# tyl.net
KiCad netlist of a schematic drawn in EAGLE
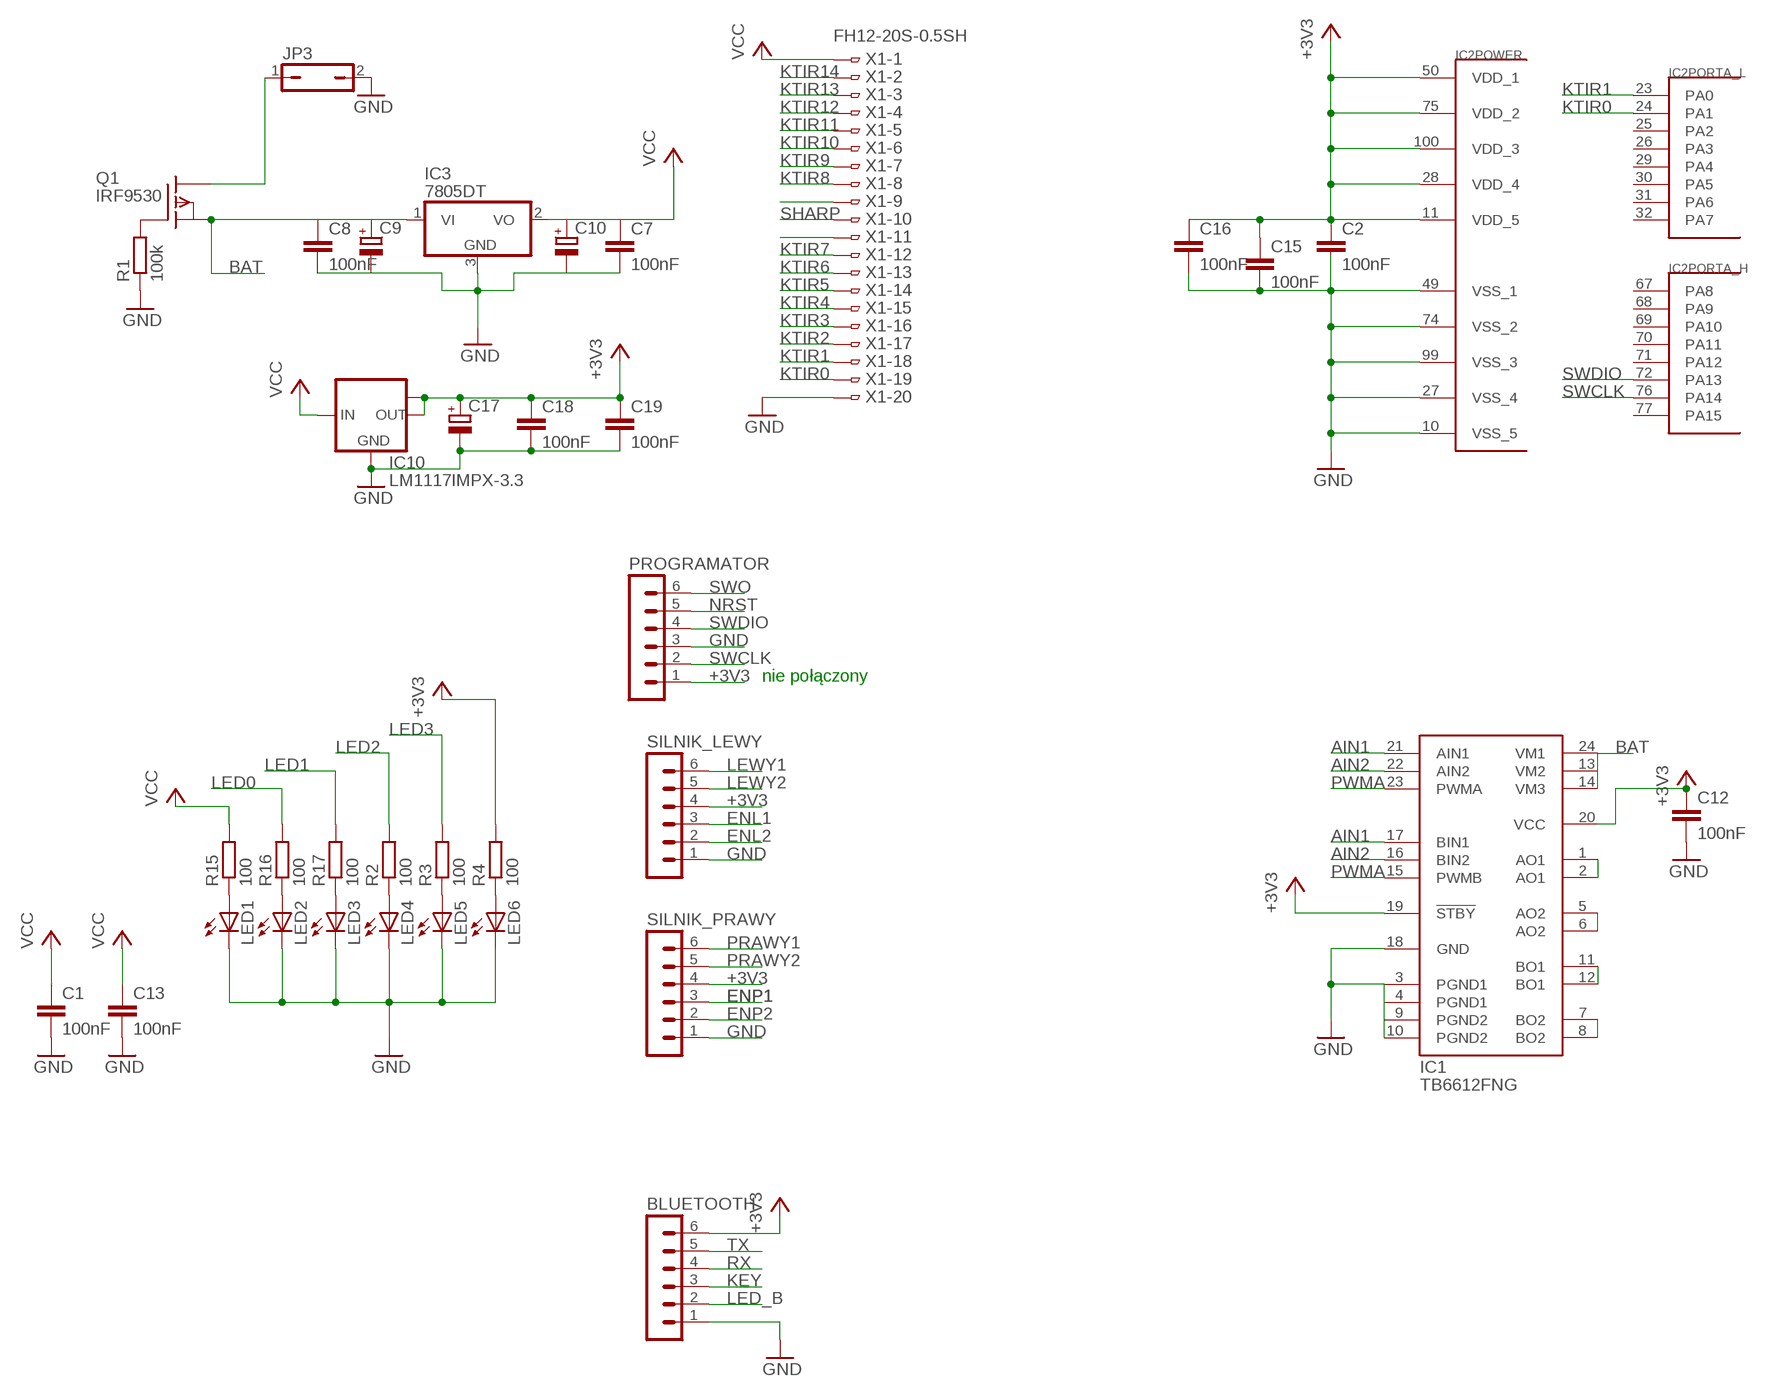
[diagram p0: schematic, sheet 1, part 1 of 2]
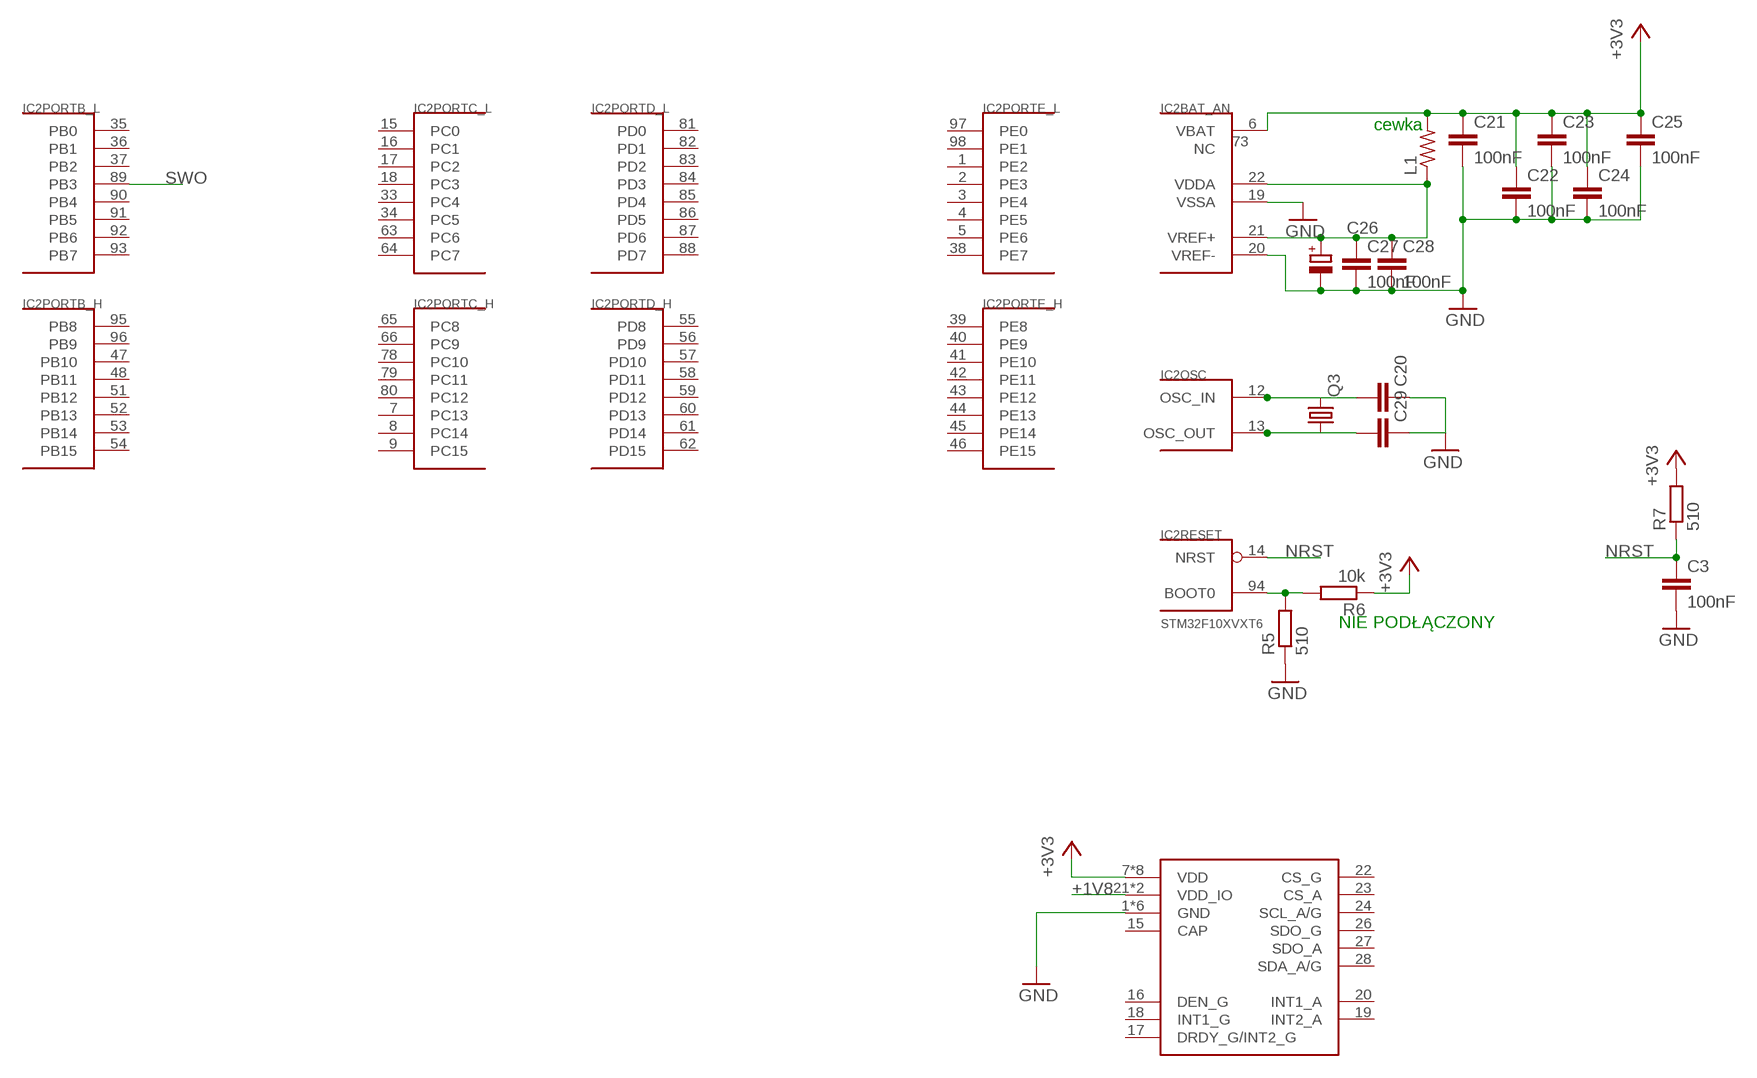
[diagram p1: schematic, sheet 1, part 2 of 2]

(export (version "E")
  (design (tool "Eeschema 10.0.6"))
  (components
    (comp (ref "BLUETOOTH")
      (value "MA06-1")
      (footprint "eagle-import:MA06-1")
      (libsource (lib "eagle-import") (part "MA06-1"))
    )
    (comp (ref "C1")
      (value "100nF")
      (footprint "eagle-import:C0603")
      (libsource (lib "eagle-import") (part "C-EUC0603"))
    )
    (comp (ref "C2")
      (value "100nF")
      (footprint "eagle-import:C0603")
      (libsource (lib "eagle-import") (part "C-EUC0603"))
    )
    (comp (ref "C3")
      (value "100nF")
      (footprint "eagle-import:C0603")
      (libsource (lib "eagle-import") (part "C-EUC0603"))
    )
    (comp (ref "C7")
      (value "100nF")
      (footprint "eagle-import:C0603")
      (libsource (lib "eagle-import") (part "C-EUC0603"))
    )
    (comp (ref "C8")
      (value "100nF")
      (footprint "eagle-import:C0603")
      (libsource (lib "eagle-import") (part "C-EUC0603"))
    )
    (comp (ref "C9")
      (value "CPOL-EUSMCA")
      (footprint "eagle-import:SMC_A")
      (libsource (lib "eagle-import") (part "CPOL-EUSMCA"))
    )
    (comp (ref "C10")
      (value "CPOL-EUSMCA")
      (footprint "eagle-import:SMC_A")
      (libsource (lib "eagle-import") (part "CPOL-EUSMCA"))
    )
    (comp (ref "C12")
      (value "100nF")
      (footprint "eagle-import:C0603")
      (libsource (lib "eagle-import") (part "C-EUC0603"))
    )
    (comp (ref "C13")
      (value "100nF")
      (footprint "eagle-import:C0603")
      (libsource (lib "eagle-import") (part "C-EUC0603"))
    )
    (comp (ref "C15")
      (value "100nF")
      (footprint "eagle-import:C0603")
      (libsource (lib "eagle-import") (part "C-EUC0603"))
    )
    (comp (ref "C16")
      (value "100nF")
      (footprint "eagle-import:C0603")
      (libsource (lib "eagle-import") (part "C-EUC0603"))
    )
    (comp (ref "C17")
      (value "CPOL-EUSMCA")
      (footprint "eagle-import:SMC_A")
      (libsource (lib "eagle-import") (part "CPOL-EUSMCA"))
    )
    (comp (ref "C18")
      (value "100nF")
      (footprint "eagle-import:C0603")
      (libsource (lib "eagle-import") (part "C-EUC0603"))
    )
    (comp (ref "C19")
      (value "100nF")
      (footprint "eagle-import:C0603")
      (libsource (lib "eagle-import") (part "C-EUC0603"))
    )
    (comp (ref "C20")
      (value "C-EUC0603")
      (footprint "eagle-import:C0603")
      (libsource (lib "eagle-import") (part "C-EUC0603"))
    )
    (comp (ref "C21")
      (value "100nF")
      (footprint "eagle-import:C0603")
      (libsource (lib "eagle-import") (part "C-EUC0603"))
    )
    (comp (ref "C22")
      (value "100nF")
      (footprint "eagle-import:C0603")
      (libsource (lib "eagle-import") (part "C-EUC0603"))
    )
    (comp (ref "C23")
      (value "100nF")
      (footprint "eagle-import:C0603")
      (libsource (lib "eagle-import") (part "C-EUC0603"))
    )
    (comp (ref "C24")
      (value "100nF")
      (footprint "eagle-import:C0603")
      (libsource (lib "eagle-import") (part "C-EUC0603"))
    )
    (comp (ref "C25")
      (value "100nF")
      (footprint "eagle-import:C0603")
      (libsource (lib "eagle-import") (part "C-EUC0603"))
    )
    (comp (ref "C26")
      (value "CPOL-EUSMCA")
      (footprint "eagle-import:SMC_A")
      (libsource (lib "eagle-import") (part "CPOL-EUSMCA"))
    )
    (comp (ref "C27")
      (value "100nF")
      (footprint "eagle-import:C0603")
      (libsource (lib "eagle-import") (part "C-EUC0603"))
    )
    (comp (ref "C28")
      (value "100nF")
      (footprint "eagle-import:C0603")
      (libsource (lib "eagle-import") (part "C-EUC0603"))
    )
    (comp (ref "C29")
      (value "C-EUC0603")
      (footprint "eagle-import:C0603")
      (libsource (lib "eagle-import") (part "C-EUC0603"))
    )
    (comp (ref "IC1")
      (value "TB6612FNG")
      (footprint "eagle-import:SSOP24")
      (libsource (lib "eagle-import") (part "TB6612FNG"))
    )
    (comp (ref "IC2")
      (value "STM32F10XVXT6")
      (footprint "eagle-import:TQFP100")
      (libsource (lib "eagle-import") (part "STM32F10XVXT6"))
    )
    (comp (ref "IC3")
      (value "7805DT")
      (footprint "eagle-import:TO252")
      (libsource (lib "eagle-import") (part "78DT05"))
    )
    (comp (ref "IC10")
      (value "LM1117IMPX-3.3")
      (footprint "eagle-import:SOT223")
      (libsource (lib "eagle-import") (part "LM1117IMPX-3.3"))
    )
    (comp (ref "JP3")
      (value "JP1Q")
      (footprint "eagle-import:JP1")
      (libsource (lib "eagle-import") (part "JP1Q"))
    )
    (comp (ref "L1")
      (value "R-US_R0805")
      (footprint "eagle-import:R0805")
      (libsource (lib "eagle-import") (part "R-US_R0805"))
    )
    (comp (ref "LED1")
      (value "LEDSML0805")
      (footprint "eagle-import:SML0805")
      (libsource (lib "eagle-import") (part "LEDSML0805"))
    )
    (comp (ref "LED2")
      (value "LEDSML0805")
      (footprint "eagle-import:SML0805")
      (libsource (lib "eagle-import") (part "LEDSML0805"))
    )
    (comp (ref "LED3")
      (value "LEDSML0805")
      (footprint "eagle-import:SML0805")
      (libsource (lib "eagle-import") (part "LEDSML0805"))
    )
    (comp (ref "LED4")
      (value "LEDSML0805")
      (footprint "eagle-import:SML0805")
      (libsource (lib "eagle-import") (part "LEDSML0805"))
    )
    (comp (ref "LED5")
      (value "LEDSML0805")
      (footprint "eagle-import:SML0805")
      (libsource (lib "eagle-import") (part "LEDSML0805"))
    )
    (comp (ref "LED6")
      (value "LEDSML0805")
      (footprint "eagle-import:SML0805")
      (libsource (lib "eagle-import") (part "LEDSML0805"))
    )
    (comp (ref "PROGRAMATOR")
      (value "MA06-1")
      (footprint "eagle-import:MA06-1")
      (libsource (lib "eagle-import") (part "MA06-1"))
    )
    (comp (ref "Q1")
      (value "IRF9530")
      (footprint "eagle-import:TO220")
      (libsource (lib "eagle-import") (part "IRF9530"))
    )
    (comp (ref "Q3")
      (value "CRYSTALSM49")
      (footprint "eagle-import:SM49")
      (libsource (lib "eagle-import") (part "CRYSTALSM49"))
    )
    (comp (ref "R1")
      (value "100k")
      (footprint "eagle-import:R0805")
      (libsource (lib "eagle-import") (part "R-EU_R0805"))
    )
    (comp (ref "R2")
      (value "100")
      (footprint "eagle-import:R0805")
      (libsource (lib "eagle-import") (part "R-EU_R0805"))
    )
    (comp (ref "R3")
      (value "100")
      (footprint "eagle-import:R0805")
      (libsource (lib "eagle-import") (part "R-EU_R0805"))
    )
    (comp (ref "R4")
      (value "100")
      (footprint "eagle-import:R0805")
      (libsource (lib "eagle-import") (part "R-EU_R0805"))
    )
    (comp (ref "R5")
      (value "510")
      (footprint "eagle-import:R0805")
      (libsource (lib "eagle-import") (part "R-EU_R0805"))
    )
    (comp (ref "R6")
      (value "10k")
      (footprint "eagle-import:R0805")
      (libsource (lib "eagle-import") (part "R-EU_R0805"))
    )
    (comp (ref "R7")
      (value "510")
      (footprint "eagle-import:R0805")
      (libsource (lib "eagle-import") (part "R-EU_R0805"))
    )
    (comp (ref "R15")
      (value "100")
      (footprint "eagle-import:R0805")
      (libsource (lib "eagle-import") (part "R-EU_R0805"))
    )
    (comp (ref "R16")
      (value "100")
      (footprint "eagle-import:R0805")
      (libsource (lib "eagle-import") (part "R-EU_R0805"))
    )
    (comp (ref "R17")
      (value "100")
      (footprint "eagle-import:R0805")
      (libsource (lib "eagle-import") (part "R-EU_R0805"))
    )
    (comp (ref "SILNIK_LEWY")
      (value "MA06-1")
      (footprint "eagle-import:MA06-1")
      (libsource (lib "eagle-import") (part "MA06-1"))
    )
    (comp (ref "SILNIK_PRAWY")
      (value "MA06-1")
      (footprint "eagle-import:MA06-1")
      (libsource (lib "eagle-import") (part "MA06-1"))
    )
    (comp (ref "U$1")
      (value "LSM330DLC")
      (footprint "eagle-import:LGA-28L")
      (libsource (lib "eagle-import") (part "LSM330DLC"))
    )
    (comp (ref "X1")
      (value "FH12-20S-0.5SH")
      (footprint "eagle-import:FH12-20S-0.5SH")
      (fields (field (name "MPN") "FH12-20S-0.5SH(55)"))
      (libsource (lib "eagle-import") (part "FH12-20S-0.5SH"))
    )
  )
  (nets
    (net (code "1") (name "+3V3") (class "Default")
      (node (ref "BLUETOOTH") (pin "6") (pinfunction "6_6") (pintype "passive"))
      (node (ref "C12") (pin "1") (pinfunction "1_1") (pintype "passive"))
      (node (ref "C15") (pin "1") (pinfunction "1_1") (pintype "passive"))
      (node (ref "C16") (pin "1") (pinfunction "1_1") (pintype "passive"))
      (node (ref "C17") (pin "+") (pinfunction "+_+") (pintype "passive"))
      (node (ref "C18") (pin "1") (pinfunction "1_1") (pintype "passive"))
      (node (ref "C19") (pin "1") (pinfunction "1_1") (pintype "passive"))
      (node (ref "C2") (pin "1") (pinfunction "1_1") (pintype "passive"))
      (node (ref "C21") (pin "1") (pinfunction "1_1") (pintype "passive"))
      (node (ref "C22") (pin "1") (pinfunction "1_1") (pintype "passive"))
      (node (ref "C23") (pin "1") (pinfunction "1_1") (pintype "passive"))
      (node (ref "C24") (pin "1") (pinfunction "1_1") (pintype "passive"))
      (node (ref "C25") (pin "1") (pinfunction "1_1") (pintype "passive"))
      (node (ref "IC1") (pin "19") (pinfunction "~{STBY}_19") (pintype "bidirectional"))
      (node (ref "IC1") (pin "20") (pinfunction "VCC_20") (pintype "bidirectional"))
      (node (ref "IC10") (pin "2") (pinfunction "OUT_2") (pintype "passive"))
      (node (ref "IC10") (pin "TAB") (pinfunction "OUT1_TAB") (pintype "passive"))
      (node (ref "IC2") (pin "100") (pinfunction "VDD_3_100") (pintype "power_in"))
      (node (ref "IC2") (pin "11") (pinfunction "VDD_5_11") (pintype "power_in"))
      (node (ref "IC2") (pin "28") (pinfunction "VDD_4_28") (pintype "power_in"))
      (node (ref "IC2") (pin "50") (pinfunction "VDD_1_50") (pintype "power_in"))
      (node (ref "IC2") (pin "6") (pinfunction "VBAT_6") (pintype "power_in"))
      (node (ref "IC2") (pin "75") (pinfunction "VDD_2_75") (pintype "power_in"))
      (node (ref "L1") (pin "2") (pinfunction "2_2") (pintype "passive"))
      (node (ref "PROGRAMATOR") (pin "1") (pinfunction "1_1") (pintype "passive"))
      (node (ref "R4") (pin "2") (pinfunction "2_2") (pintype "passive"))
      (node (ref "R6") (pin "1") (pinfunction "1_1") (pintype "passive"))
      (node (ref "R7") (pin "2") (pinfunction "2_2") (pintype "passive"))
      (node (ref "SILNIK_LEWY") (pin "4") (pinfunction "4_4") (pintype "passive"))
      (node (ref "SILNIK_PRAWY") (pin "4") (pinfunction "4_4") (pintype "passive"))
      (node (ref "U$1") (pin "10") (pinfunction "VDD_10") (pintype "power_in"))
      (node (ref "U$1") (pin "11") (pinfunction "VDD_11") (pintype "power_in"))
      (node (ref "U$1") (pin "12") (pinfunction "VDD_12") (pintype "power_in"))
      (node (ref "U$1") (pin "13") (pinfunction "VDD_13") (pintype "power_in"))
      (node (ref "U$1") (pin "14") (pinfunction "VDD_14") (pintype "power_in"))
      (node (ref "U$1") (pin "7") (pinfunction "VDD_7") (pintype "power_in"))
      (node (ref "U$1") (pin "8") (pinfunction "VDD_8") (pintype "power_in"))
      (node (ref "U$1") (pin "9") (pinfunction "VDD_9") (pintype "power_in"))
    )
    (net (code "2") (name "/+1V8") (class "Default")
      (node (ref "U$1") (pin "21") (pinfunction "VDD_IO_21") (pintype "power_in"))
      (node (ref "U$1") (pin "25") (pinfunction "VDD_IO_25") (pintype "power_in"))
    )
    (net (code "3") (name "/AIN1") (class "Default")
      (node (ref "IC1") (pin "17") (pinfunction "BIN1_17") (pintype "bidirectional"))
      (node (ref "IC1") (pin "21") (pinfunction "AIN1_21") (pintype "bidirectional"))
    )
    (net (code "4") (name "/AIN2") (class "Default")
      (node (ref "IC1") (pin "16") (pinfunction "BIN2_16") (pintype "bidirectional"))
      (node (ref "IC1") (pin "22") (pinfunction "AIN2_22") (pintype "bidirectional"))
    )
    (net (code "5") (name "/BAT") (class "Default")
      (node (ref "C8") (pin "1") (pinfunction "1_1") (pintype "passive"))
      (node (ref "C9") (pin "+") (pinfunction "+_+") (pintype "passive"))
      (node (ref "IC1") (pin "13") (pinfunction "VM2_13") (pintype "bidirectional"))
      (node (ref "IC1") (pin "14") (pinfunction "VM3_14") (pintype "bidirectional"))
      (node (ref "IC1") (pin "24") (pinfunction "VM1_24") (pintype "bidirectional"))
      (node (ref "IC3") (pin "1") (pinfunction "VI_1") (pintype "input"))
      (node (ref "Q1") (pin "3") (pinfunction "S_3") (pintype "passive"))
    )
    (net (code "6") (name "/ENL1") (class "Default")
      (node (ref "SILNIK_LEWY") (pin "3") (pinfunction "3_3") (pintype "passive"))
    )
    (net (code "7") (name "/ENL2") (class "Default")
      (node (ref "SILNIK_LEWY") (pin "2") (pinfunction "2_2") (pintype "passive"))
    )
    (net (code "8") (name "/ENP1") (class "Default")
      (node (ref "SILNIK_PRAWY") (pin "3") (pinfunction "3_3") (pintype "passive"))
    )
    (net (code "9") (name "/ENP2") (class "Default")
      (node (ref "SILNIK_PRAWY") (pin "2") (pinfunction "2_2") (pintype "passive"))
    )
    (net (code "10") (name "/KEY") (class "Default")
      (node (ref "BLUETOOTH") (pin "3") (pinfunction "3_3") (pintype "passive"))
    )
    (net (code "11") (name "/KTIR0") (class "Default")
      (node (ref "IC2") (pin "24") (pinfunction "PA1_24") (pintype "bidirectional"))
      (node (ref "X1") (pin "19") (pinfunction "1_19") (pintype "passive"))
    )
    (net (code "12") (name "/KTIR1") (class "Default")
      (node (ref "IC2") (pin "23") (pinfunction "PA0_23") (pintype "bidirectional"))
      (node (ref "X1") (pin "18") (pinfunction "1_18") (pintype "passive"))
    )
    (net (code "13") (name "/KTIR2") (class "Default")
      (node (ref "X1") (pin "17") (pinfunction "1_17") (pintype "passive"))
    )
    (net (code "14") (name "/KTIR3") (class "Default")
      (node (ref "X1") (pin "16") (pinfunction "1_16") (pintype "passive"))
    )
    (net (code "15") (name "/KTIR4") (class "Default")
      (node (ref "X1") (pin "15") (pinfunction "1_15") (pintype "passive"))
    )
    (net (code "16") (name "/KTIR5") (class "Default")
      (node (ref "X1") (pin "14") (pinfunction "1_14") (pintype "passive"))
    )
    (net (code "17") (name "/KTIR6") (class "Default")
      (node (ref "X1") (pin "13") (pinfunction "1_13") (pintype "passive"))
    )
    (net (code "18") (name "/KTIR7") (class "Default")
      (node (ref "X1") (pin "12") (pinfunction "1_12") (pintype "passive"))
    )
    (net (code "19") (name "/KTIR8") (class "Default")
      (node (ref "X1") (pin "8") (pinfunction "1_8") (pintype "passive"))
    )
    (net (code "20") (name "/KTIR9") (class "Default")
      (node (ref "X1") (pin "7") (pinfunction "1_7") (pintype "passive"))
    )
    (net (code "21") (name "/KTIR10") (class "Default")
      (node (ref "X1") (pin "6") (pinfunction "1_6") (pintype "passive"))
    )
    (net (code "22") (name "/KTIR11") (class "Default")
      (node (ref "X1") (pin "5") (pinfunction "1_5") (pintype "passive"))
    )
    (net (code "23") (name "/KTIR12") (class "Default")
      (node (ref "X1") (pin "4") (pinfunction "1_4") (pintype "passive"))
    )
    (net (code "24") (name "/KTIR13") (class "Default")
      (node (ref "X1") (pin "3") (pinfunction "1_3") (pintype "passive"))
    )
    (net (code "25") (name "/KTIR14") (class "Default")
      (node (ref "X1") (pin "2") (pinfunction "1_2") (pintype "passive"))
    )
    (net (code "26") (name "/LED0") (class "Default")
      (node (ref "R16") (pin "2") (pinfunction "2_2") (pintype "passive"))
    )
    (net (code "27") (name "/LED1") (class "Default")
      (node (ref "R17") (pin "2") (pinfunction "2_2") (pintype "passive"))
    )
    (net (code "28") (name "/LED2") (class "Default")
      (node (ref "R2") (pin "2") (pinfunction "2_2") (pintype "passive"))
    )
    (net (code "29") (name "/LED3") (class "Default")
      (node (ref "R3") (pin "2") (pinfunction "2_2") (pintype "passive"))
    )
    (net (code "30") (name "/LED_B") (class "Default")
      (node (ref "BLUETOOTH") (pin "2") (pinfunction "2_2") (pintype "passive"))
    )
    (net (code "31") (name "/LEWY1") (class "Default")
      (node (ref "IC1") (pin "11") (pinfunction "BO1_11") (pintype "bidirectional"))
      (node (ref "IC1") (pin "12") (pinfunction "BO1_12") (pintype "bidirectional"))
      (node (ref "SILNIK_LEWY") (pin "6") (pinfunction "6_6") (pintype "passive"))
    )
    (net (code "32") (name "/LEWY2") (class "Default")
      (node (ref "IC1") (pin "7") (pinfunction "BO2_7") (pintype "bidirectional"))
      (node (ref "IC1") (pin "8") (pinfunction "BO2_8") (pintype "bidirectional"))
      (node (ref "SILNIK_LEWY") (pin "5") (pinfunction "5_5") (pintype "passive"))
    )
    (net (code "33") (name "/NRST") (class "Default")
      (node (ref "C3") (pin "1") (pinfunction "1_1") (pintype "passive"))
      (node (ref "IC2") (pin "14") (pinfunction "NRST_14") (pintype "input"))
      (node (ref "PROGRAMATOR") (pin "5") (pinfunction "5_5") (pintype "passive"))
      (node (ref "R7") (pin "1") (pinfunction "1_1") (pintype "passive"))
    )
    (net (code "34") (name "/PRAWY1") (class "Default")
      (node (ref "SILNIK_PRAWY") (pin "6") (pinfunction "6_6") (pintype "passive"))
    )
    (net (code "35") (name "/PRAWY2") (class "Default")
      (node (ref "SILNIK_PRAWY") (pin "5") (pinfunction "5_5") (pintype "passive"))
    )
    (net (code "36") (name "/PWMA") (class "Default")
      (node (ref "IC1") (pin "15") (pinfunction "PWMB_15") (pintype "bidirectional"))
      (node (ref "IC1") (pin "23") (pinfunction "PWMA_23") (pintype "bidirectional"))
    )
    (net (code "37") (name "/RX") (class "Default")
      (node (ref "BLUETOOTH") (pin "4") (pinfunction "4_4") (pintype "passive"))
    )
    (net (code "38") (name "/SHARP") (class "Default")
      (node (ref "X1") (pin "10") (pinfunction "1_10") (pintype "passive"))
    )
    (net (code "39") (name "/SWCLK") (class "Default")
      (node (ref "IC2") (pin "76") (pinfunction "PA14_76") (pintype "bidirectional"))
      (node (ref "PROGRAMATOR") (pin "2") (pinfunction "2_2") (pintype "passive"))
    )
    (net (code "40") (name "/SWDIO") (class "Default")
      (node (ref "IC2") (pin "72") (pinfunction "PA13_72") (pintype "bidirectional"))
      (node (ref "PROGRAMATOR") (pin "4") (pinfunction "4_4") (pintype "passive"))
    )
    (net (code "41") (name "/SWO") (class "Default")
      (node (ref "IC2") (pin "89") (pinfunction "PB3_89") (pintype "bidirectional"))
      (node (ref "PROGRAMATOR") (pin "6") (pinfunction "6_6") (pintype "passive"))
    )
    (net (code "42") (name "/TX") (class "Default")
      (node (ref "BLUETOOTH") (pin "5") (pinfunction "5_5") (pintype "passive"))
    )
    (net (code "43") (name "GND") (class "Default")
      (node (ref "BLUETOOTH") (pin "1") (pinfunction "1_1") (pintype "passive"))
      (node (ref "C1") (pin "2") (pinfunction "2_2") (pintype "passive"))
      (node (ref "C10") (pin "-") (pinfunction "-_-") (pintype "passive"))
      (node (ref "C12") (pin "2") (pinfunction "2_2") (pintype "passive"))
      (node (ref "C13") (pin "2") (pinfunction "2_2") (pintype "passive"))
      (node (ref "C15") (pin "2") (pinfunction "2_2") (pintype "passive"))
      (node (ref "C16") (pin "2") (pinfunction "2_2") (pintype "passive"))
      (node (ref "C17") (pin "-") (pinfunction "-_-") (pintype "passive"))
      (node (ref "C18") (pin "2") (pinfunction "2_2") (pintype "passive"))
      (node (ref "C19") (pin "2") (pinfunction "2_2") (pintype "passive"))
      (node (ref "C2") (pin "2") (pinfunction "2_2") (pintype "passive"))
      (node (ref "C20") (pin "1") (pinfunction "1_1") (pintype "passive"))
      (node (ref "C21") (pin "2") (pinfunction "2_2") (pintype "passive"))
      (node (ref "C22") (pin "2") (pinfunction "2_2") (pintype "passive"))
      (node (ref "C23") (pin "2") (pinfunction "2_2") (pintype "passive"))
      (node (ref "C24") (pin "2") (pinfunction "2_2") (pintype "passive"))
      (node (ref "C25") (pin "2") (pinfunction "2_2") (pintype "passive"))
      (node (ref "C26") (pin "-") (pinfunction "-_-") (pintype "passive"))
      (node (ref "C27") (pin "2") (pinfunction "2_2") (pintype "passive"))
      (node (ref "C28") (pin "2") (pinfunction "2_2") (pintype "passive"))
      (node (ref "C29") (pin "1") (pinfunction "1_1") (pintype "passive"))
      (node (ref "C3") (pin "2") (pinfunction "2_2") (pintype "passive"))
      (node (ref "C7") (pin "2") (pinfunction "2_2") (pintype "passive"))
      (node (ref "C8") (pin "2") (pinfunction "2_2") (pintype "passive"))
      (node (ref "C9") (pin "-") (pinfunction "-_-") (pintype "passive"))
      (node (ref "IC1") (pin "10") (pinfunction "PGND2_10") (pintype "bidirectional"))
      (node (ref "IC1") (pin "18") (pinfunction "GND_18") (pintype "bidirectional"))
      (node (ref "IC1") (pin "3") (pinfunction "PGND1_3") (pintype "bidirectional"))
      (node (ref "IC1") (pin "4") (pinfunction "PGND1_4") (pintype "bidirectional"))
      (node (ref "IC1") (pin "9") (pinfunction "PGND2_9") (pintype "bidirectional"))
      (node (ref "IC10") (pin "1") (pinfunction "GND_1") (pintype "input"))
      (node (ref "IC2") (pin "10") (pinfunction "VSS_5_10") (pintype "power_in"))
      (node (ref "IC2") (pin "19") (pinfunction "VSSA_19") (pintype "power_in"))
      (node (ref "IC2") (pin "20") (pinfunction "VREF-_20") (pintype "input"))
      (node (ref "IC2") (pin "27") (pinfunction "VSS_4_27") (pintype "power_in"))
      (node (ref "IC2") (pin "49") (pinfunction "VSS_1_49") (pintype "power_in"))
      (node (ref "IC2") (pin "74") (pinfunction "VSS_2_74") (pintype "power_in"))
      (node (ref "IC2") (pin "99") (pinfunction "VSS_3_99") (pintype "power_in"))
      (node (ref "IC3") (pin "3") (pinfunction "GND_3") (pintype "passive"))
      (node (ref "JP3") (pin "2") (pinfunction "2_2") (pintype "passive"))
      (node (ref "LED1") (pin "C") (pinfunction "C_C") (pintype "passive"))
      (node (ref "LED2") (pin "C") (pinfunction "C_C") (pintype "passive"))
      (node (ref "LED3") (pin "C") (pinfunction "C_C") (pintype "passive"))
      (node (ref "LED4") (pin "C") (pinfunction "C_C") (pintype "passive"))
      (node (ref "LED5") (pin "C") (pinfunction "C_C") (pintype "passive"))
      (node (ref "LED6") (pin "C") (pinfunction "C_C") (pintype "passive"))
      (node (ref "PROGRAMATOR") (pin "3") (pinfunction "3_3") (pintype "passive"))
      (node (ref "R1") (pin "1") (pinfunction "1_1") (pintype "passive"))
      (node (ref "R5") (pin "1") (pinfunction "1_1") (pintype "passive"))
      (node (ref "SILNIK_LEWY") (pin "1") (pinfunction "1_1") (pintype "passive"))
      (node (ref "SILNIK_PRAWY") (pin "1") (pinfunction "1_1") (pintype "passive"))
      (node (ref "U$1") (pin "1") (pinfunction "GND_1") (pintype "power_in"))
      (node (ref "U$1") (pin "2") (pinfunction "GND_2") (pintype "power_in"))
      (node (ref "U$1") (pin "3") (pinfunction "GND_3") (pintype "power_in"))
      (node (ref "U$1") (pin "4") (pinfunction "GND_4") (pintype "power_in"))
      (node (ref "U$1") (pin "5") (pinfunction "GND_5") (pintype "power_in"))
      (node (ref "U$1") (pin "6") (pinfunction "GND_6") (pintype "power_in"))
      (node (ref "X1") (pin "20") (pinfunction "1_20") (pintype "passive"))
    )
    (net (code "44") (name "Net-(IC1-AO1-Pad1)") (class "Default")
      (node (ref "IC1") (pin "1") (pinfunction "AO1_1") (pintype "bidirectional"))
      (node (ref "IC1") (pin "2") (pinfunction "AO1_2") (pintype "bidirectional"))
    )
    (net (code "45") (name "Net-(IC1-AO2-Pad5)") (class "Default")
      (node (ref "IC1") (pin "5") (pinfunction "AO2_5") (pintype "bidirectional"))
      (node (ref "IC1") (pin "6") (pinfunction "AO2_6") (pintype "bidirectional"))
    )
    (net (code "46") (name "Net-(IC2A-VDDA)") (class "Default")
      (node (ref "C26") (pin "+") (pinfunction "+_+") (pintype "passive"))
      (node (ref "C27") (pin "1") (pinfunction "1_1") (pintype "passive"))
      (node (ref "C28") (pin "1") (pinfunction "1_1") (pintype "passive"))
      (node (ref "IC2") (pin "21") (pinfunction "VREF+_21") (pintype "input"))
      (node (ref "IC2") (pin "22") (pinfunction "VDDA_22") (pintype "power_in"))
      (node (ref "L1") (pin "1") (pinfunction "1_1") (pintype "passive"))
    )
    (net (code "47") (name "Net-(IC2B-OSC_IN)") (class "Default")
      (node (ref "C20") (pin "2") (pinfunction "2_2") (pintype "passive"))
      (node (ref "IC2") (pin "12") (pinfunction "OSC_IN_12") (pintype "input"))
      (node (ref "Q3") (pin "2") (pinfunction "2_2") (pintype "passive"))
    )
    (net (code "48") (name "Net-(IC2B-OSC_OUT)") (class "Default")
      (node (ref "C29") (pin "2") (pinfunction "2_2") (pintype "passive"))
      (node (ref "IC2") (pin "13") (pinfunction "OSC_OUT_13") (pintype "output"))
      (node (ref "Q3") (pin "1") (pinfunction "1_1") (pintype "passive"))
    )
    (net (code "49") (name "Net-(IC2N-BOOT0)") (class "Default")
      (node (ref "IC2") (pin "94") (pinfunction "BOOT0_94") (pintype "input"))
      (node (ref "R5") (pin "2") (pinfunction "2_2") (pintype "passive"))
      (node (ref "R6") (pin "2") (pinfunction "2_2") (pintype "passive"))
    )
    (net (code "50") (name "Net-(LED1-PadA)") (class "Default")
      (node (ref "LED1") (pin "A") (pinfunction "A_A") (pintype "passive"))
      (node (ref "R15") (pin "1") (pinfunction "1_1") (pintype "passive"))
    )
    (net (code "51") (name "Net-(LED2-PadA)") (class "Default")
      (node (ref "LED2") (pin "A") (pinfunction "A_A") (pintype "passive"))
      (node (ref "R16") (pin "1") (pinfunction "1_1") (pintype "passive"))
    )
    (net (code "52") (name "Net-(LED3-PadA)") (class "Default")
      (node (ref "LED3") (pin "A") (pinfunction "A_A") (pintype "passive"))
      (node (ref "R17") (pin "1") (pinfunction "1_1") (pintype "passive"))
    )
    (net (code "53") (name "Net-(LED4-PadA)") (class "Default")
      (node (ref "LED4") (pin "A") (pinfunction "A_A") (pintype "passive"))
      (node (ref "R2") (pin "1") (pinfunction "1_1") (pintype "passive"))
    )
    (net (code "54") (name "Net-(LED5-PadA)") (class "Default")
      (node (ref "LED5") (pin "A") (pinfunction "A_A") (pintype "passive"))
      (node (ref "R3") (pin "1") (pinfunction "1_1") (pintype "passive"))
    )
    (net (code "55") (name "Net-(LED6-PadA)") (class "Default")
      (node (ref "LED6") (pin "A") (pinfunction "A_A") (pintype "passive"))
      (node (ref "R4") (pin "1") (pinfunction "1_1") (pintype "passive"))
    )
    (net (code "56") (name "Net-(Q1-D)") (class "Default")
      (node (ref "JP3") (pin "1") (pinfunction "1_1") (pintype "passive"))
      (node (ref "Q1") (pin "2") (pinfunction "D_2") (pintype "passive"))
    )
    (net (code "57") (name "Net-(Q1-G)") (class "Default")
      (node (ref "Q1") (pin "1") (pinfunction "G_1") (pintype "passive"))
      (node (ref "R1") (pin "2") (pinfunction "2_2") (pintype "passive"))
    )
    (net (code "58") (name "VCC") (class "Default")
      (node (ref "C1") (pin "1") (pinfunction "1_1") (pintype "passive"))
      (node (ref "C10") (pin "+") (pinfunction "+_+") (pintype "passive"))
      (node (ref "C13") (pin "1") (pinfunction "1_1") (pintype "passive"))
      (node (ref "C7") (pin "1") (pinfunction "1_1") (pintype "passive"))
      (node (ref "IC10") (pin "3") (pinfunction "IN_3") (pintype "input"))
      (node (ref "IC3") (pin "2") (pinfunction "VO_2") (pintype "passive"))
      (node (ref "R15") (pin "2") (pinfunction "2_2") (pintype "passive"))
      (node (ref "X1") (pin "1") (pinfunction "1_1") (pintype "passive"))
    )
    (net (code "59") (name "unconnected-(IC2A-NC-Pad73)") (class "Default")
      (node (ref "IC2") (pin "73") (pinfunction "NC_73") (pintype "no_connect"))
    )
    (net (code "60") (name "unconnected-(IC2C-PA8-Pad67)") (class "Default")
      (node (ref "IC2") (pin "67") (pinfunction "PA8_67") (pintype "bidirectional"))
    )
    (net (code "61") (name "unconnected-(IC2C-PA9-Pad68)") (class "Default")
      (node (ref "IC2") (pin "68") (pinfunction "PA9_68") (pintype "bidirectional"))
    )
    (net (code "62") (name "unconnected-(IC2C-PA10-Pad69)") (class "Default")
      (node (ref "IC2") (pin "69") (pinfunction "PA10_69") (pintype "bidirectional"))
    )
    (net (code "63") (name "unconnected-(IC2C-PA11-Pad70)") (class "Default")
      (node (ref "IC2") (pin "70") (pinfunction "PA11_70") (pintype "bidirectional"))
    )
    (net (code "64") (name "unconnected-(IC2C-PA12-Pad71)") (class "Default")
      (node (ref "IC2") (pin "71") (pinfunction "PA12_71") (pintype "bidirectional"))
    )
    (net (code "65") (name "unconnected-(IC2C-PA15-Pad77)") (class "Default")
      (node (ref "IC2") (pin "77") (pinfunction "PA15_77") (pintype "bidirectional"))
    )
    (net (code "66") (name "unconnected-(IC2D-PA2-Pad25)") (class "Default")
      (node (ref "IC2") (pin "25") (pinfunction "PA2_25") (pintype "bidirectional"))
    )
    (net (code "67") (name "unconnected-(IC2D-PA3-Pad26)") (class "Default")
      (node (ref "IC2") (pin "26") (pinfunction "PA3_26") (pintype "bidirectional"))
    )
    (net (code "68") (name "unconnected-(IC2D-PA4-Pad29)") (class "Default")
      (node (ref "IC2") (pin "29") (pinfunction "PA4_29") (pintype "bidirectional"))
    )
    (net (code "69") (name "unconnected-(IC2D-PA5-Pad30)") (class "Default")
      (node (ref "IC2") (pin "30") (pinfunction "PA5_30") (pintype "bidirectional"))
    )
    (net (code "70") (name "unconnected-(IC2D-PA6-Pad31)") (class "Default")
      (node (ref "IC2") (pin "31") (pinfunction "PA6_31") (pintype "bidirectional"))
    )
    (net (code "71") (name "unconnected-(IC2D-PA7-Pad32)") (class "Default")
      (node (ref "IC2") (pin "32") (pinfunction "PA7_32") (pintype "bidirectional"))
    )
    (net (code "72") (name "unconnected-(IC2E-PB8-Pad95)") (class "Default")
      (node (ref "IC2") (pin "95") (pinfunction "PB8_95") (pintype "bidirectional"))
    )
    (net (code "73") (name "unconnected-(IC2E-PB9-Pad96)") (class "Default")
      (node (ref "IC2") (pin "96") (pinfunction "PB9_96") (pintype "bidirectional"))
    )
    (net (code "74") (name "unconnected-(IC2E-PB10-Pad47)") (class "Default")
      (node (ref "IC2") (pin "47") (pinfunction "PB10_47") (pintype "bidirectional"))
    )
    (net (code "75") (name "unconnected-(IC2E-PB11-Pad48)") (class "Default")
      (node (ref "IC2") (pin "48") (pinfunction "PB11_48") (pintype "bidirectional"))
    )
    (net (code "76") (name "unconnected-(IC2E-PB12-Pad51)") (class "Default")
      (node (ref "IC2") (pin "51") (pinfunction "PB12_51") (pintype "bidirectional"))
    )
    (net (code "77") (name "unconnected-(IC2E-PB13-Pad52)") (class "Default")
      (node (ref "IC2") (pin "52") (pinfunction "PB13_52") (pintype "bidirectional"))
    )
    (net (code "78") (name "unconnected-(IC2E-PB14-Pad53)") (class "Default")
      (node (ref "IC2") (pin "53") (pinfunction "PB14_53") (pintype "bidirectional"))
    )
    (net (code "79") (name "unconnected-(IC2E-PB15-Pad54)") (class "Default")
      (node (ref "IC2") (pin "54") (pinfunction "PB15_54") (pintype "bidirectional"))
    )
    (net (code "80") (name "unconnected-(IC2F-PB0-Pad35)") (class "Default")
      (node (ref "IC2") (pin "35") (pinfunction "PB0_35") (pintype "bidirectional"))
    )
    (net (code "81") (name "unconnected-(IC2F-PB1-Pad36)") (class "Default")
      (node (ref "IC2") (pin "36") (pinfunction "PB1_36") (pintype "bidirectional"))
    )
    (net (code "82") (name "unconnected-(IC2F-PB2-Pad37)") (class "Default")
      (node (ref "IC2") (pin "37") (pinfunction "PB2_37") (pintype "bidirectional"))
    )
    (net (code "83") (name "unconnected-(IC2F-PB4-Pad90)") (class "Default")
      (node (ref "IC2") (pin "90") (pinfunction "PB4_90") (pintype "bidirectional"))
    )
    (net (code "84") (name "unconnected-(IC2F-PB5-Pad91)") (class "Default")
      (node (ref "IC2") (pin "91") (pinfunction "PB5_91") (pintype "bidirectional"))
    )
    (net (code "85") (name "unconnected-(IC2F-PB6-Pad92)") (class "Default")
      (node (ref "IC2") (pin "92") (pinfunction "PB6_92") (pintype "bidirectional"))
    )
    (net (code "86") (name "unconnected-(IC2F-PB7-Pad93)") (class "Default")
      (node (ref "IC2") (pin "93") (pinfunction "PB7_93") (pintype "bidirectional"))
    )
    (net (code "87") (name "unconnected-(IC2G-PC8-Pad65)") (class "Default")
      (node (ref "IC2") (pin "65") (pinfunction "PC8_65") (pintype "bidirectional"))
    )
    (net (code "88") (name "unconnected-(IC2G-PC9-Pad66)") (class "Default")
      (node (ref "IC2") (pin "66") (pinfunction "PC9_66") (pintype "bidirectional"))
    )
    (net (code "89") (name "unconnected-(IC2G-PC10-Pad78)") (class "Default")
      (node (ref "IC2") (pin "78") (pinfunction "PC10_78") (pintype "bidirectional"))
    )
    (net (code "90") (name "unconnected-(IC2G-PC11-Pad79)") (class "Default")
      (node (ref "IC2") (pin "79") (pinfunction "PC11_79") (pintype "bidirectional"))
    )
    (net (code "91") (name "unconnected-(IC2G-PC12-Pad80)") (class "Default")
      (node (ref "IC2") (pin "80") (pinfunction "PC12_80") (pintype "bidirectional"))
    )
    (net (code "92") (name "unconnected-(IC2G-PC13-Pad7)") (class "Default")
      (node (ref "IC2") (pin "7") (pinfunction "PC13_7") (pintype "bidirectional"))
    )
    (net (code "93") (name "unconnected-(IC2G-PC14-Pad8)") (class "Default")
      (node (ref "IC2") (pin "8") (pinfunction "PC14_8") (pintype "bidirectional"))
    )
    (net (code "94") (name "unconnected-(IC2G-PC15-Pad9)") (class "Default")
      (node (ref "IC2") (pin "9") (pinfunction "PC15_9") (pintype "bidirectional"))
    )
    (net (code "95") (name "unconnected-(IC2H-PC0-Pad15)") (class "Default")
      (node (ref "IC2") (pin "15") (pinfunction "PC0_15") (pintype "bidirectional"))
    )
    (net (code "96") (name "unconnected-(IC2H-PC1-Pad16)") (class "Default")
      (node (ref "IC2") (pin "16") (pinfunction "PC1_16") (pintype "bidirectional"))
    )
    (net (code "97") (name "unconnected-(IC2H-PC2-Pad17)") (class "Default")
      (node (ref "IC2") (pin "17") (pinfunction "PC2_17") (pintype "bidirectional"))
    )
    (net (code "98") (name "unconnected-(IC2H-PC3-Pad18)") (class "Default")
      (node (ref "IC2") (pin "18") (pinfunction "PC3_18") (pintype "bidirectional"))
    )
    (net (code "99") (name "unconnected-(IC2H-PC4-Pad33)") (class "Default")
      (node (ref "IC2") (pin "33") (pinfunction "PC4_33") (pintype "bidirectional"))
    )
    (net (code "100") (name "unconnected-(IC2H-PC5-Pad34)") (class "Default")
      (node (ref "IC2") (pin "34") (pinfunction "PC5_34") (pintype "bidirectional"))
    )
    (net (code "101") (name "unconnected-(IC2H-PC6-Pad63)") (class "Default")
      (node (ref "IC2") (pin "63") (pinfunction "PC6_63") (pintype "bidirectional"))
    )
    (net (code "102") (name "unconnected-(IC2H-PC7-Pad64)") (class "Default")
      (node (ref "IC2") (pin "64") (pinfunction "PC7_64") (pintype "bidirectional"))
    )
    (net (code "103") (name "unconnected-(IC2I-PD8-Pad55)") (class "Default")
      (node (ref "IC2") (pin "55") (pinfunction "PD8_55") (pintype "bidirectional"))
    )
    (net (code "104") (name "unconnected-(IC2I-PD9-Pad56)") (class "Default")
      (node (ref "IC2") (pin "56") (pinfunction "PD9_56") (pintype "bidirectional"))
    )
    (net (code "105") (name "unconnected-(IC2I-PD10-Pad57)") (class "Default")
      (node (ref "IC2") (pin "57") (pinfunction "PD10_57") (pintype "bidirectional"))
    )
    (net (code "106") (name "unconnected-(IC2I-PD11-Pad58)") (class "Default")
      (node (ref "IC2") (pin "58") (pinfunction "PD11_58") (pintype "bidirectional"))
    )
    (net (code "107") (name "unconnected-(IC2I-PD12-Pad59)") (class "Default")
      (node (ref "IC2") (pin "59") (pinfunction "PD12_59") (pintype "bidirectional"))
    )
    (net (code "108") (name "unconnected-(IC2I-PD13-Pad60)") (class "Default")
      (node (ref "IC2") (pin "60") (pinfunction "PD13_60") (pintype "bidirectional"))
    )
    (net (code "109") (name "unconnected-(IC2I-PD14-Pad61)") (class "Default")
      (node (ref "IC2") (pin "61") (pinfunction "PD14_61") (pintype "bidirectional"))
    )
    (net (code "110") (name "unconnected-(IC2I-PD15-Pad62)") (class "Default")
      (node (ref "IC2") (pin "62") (pinfunction "PD15_62") (pintype "bidirectional"))
    )
    (net (code "111") (name "unconnected-(IC2J-PD0-Pad81)") (class "Default")
      (node (ref "IC2") (pin "81") (pinfunction "PD0_81") (pintype "bidirectional"))
    )
    (net (code "112") (name "unconnected-(IC2J-PD1-Pad82)") (class "Default")
      (node (ref "IC2") (pin "82") (pinfunction "PD1_82") (pintype "bidirectional"))
    )
    (net (code "113") (name "unconnected-(IC2J-PD2-Pad83)") (class "Default")
      (node (ref "IC2") (pin "83") (pinfunction "PD2_83") (pintype "bidirectional"))
    )
    (net (code "114") (name "unconnected-(IC2J-PD3-Pad84)") (class "Default")
      (node (ref "IC2") (pin "84") (pinfunction "PD3_84") (pintype "bidirectional"))
    )
    (net (code "115") (name "unconnected-(IC2J-PD4-Pad85)") (class "Default")
      (node (ref "IC2") (pin "85") (pinfunction "PD4_85") (pintype "bidirectional"))
    )
    (net (code "116") (name "unconnected-(IC2J-PD5-Pad86)") (class "Default")
      (node (ref "IC2") (pin "86") (pinfunction "PD5_86") (pintype "bidirectional"))
    )
    (net (code "117") (name "unconnected-(IC2J-PD6-Pad87)") (class "Default")
      (node (ref "IC2") (pin "87") (pinfunction "PD6_87") (pintype "bidirectional"))
    )
    (net (code "118") (name "unconnected-(IC2J-PD7-Pad88)") (class "Default")
      (node (ref "IC2") (pin "88") (pinfunction "PD7_88") (pintype "bidirectional"))
    )
    (net (code "119") (name "unconnected-(IC2K-PE8-Pad39)") (class "Default")
      (node (ref "IC2") (pin "39") (pinfunction "PE8_39") (pintype "bidirectional"))
    )
    (net (code "120") (name "unconnected-(IC2K-PE9-Pad40)") (class "Default")
      (node (ref "IC2") (pin "40") (pinfunction "PE9_40") (pintype "bidirectional"))
    )
    (net (code "121") (name "unconnected-(IC2K-PE10-Pad41)") (class "Default")
      (node (ref "IC2") (pin "41") (pinfunction "PE10_41") (pintype "bidirectional"))
    )
    (net (code "122") (name "unconnected-(IC2K-PE11-Pad42)") (class "Default")
      (node (ref "IC2") (pin "42") (pinfunction "PE11_42") (pintype "bidirectional"))
    )
    (net (code "123") (name "unconnected-(IC2K-PE12-Pad43)") (class "Default")
      (node (ref "IC2") (pin "43") (pinfunction "PE12_43") (pintype "bidirectional"))
    )
    (net (code "124") (name "unconnected-(IC2K-PE13-Pad44)") (class "Default")
      (node (ref "IC2") (pin "44") (pinfunction "PE13_44") (pintype "bidirectional"))
    )
    (net (code "125") (name "unconnected-(IC2K-PE14-Pad45)") (class "Default")
      (node (ref "IC2") (pin "45") (pinfunction "PE14_45") (pintype "bidirectional"))
    )
    (net (code "126") (name "unconnected-(IC2K-PE15-Pad46)") (class "Default")
      (node (ref "IC2") (pin "46") (pinfunction "PE15_46") (pintype "bidirectional"))
    )
    (net (code "127") (name "unconnected-(IC2L-PE0-Pad97)") (class "Default")
      (node (ref "IC2") (pin "97") (pinfunction "PE0_97") (pintype "bidirectional"))
    )
    (net (code "128") (name "unconnected-(IC2L-PE1-Pad98)") (class "Default")
      (node (ref "IC2") (pin "98") (pinfunction "PE1_98") (pintype "bidirectional"))
    )
    (net (code "129") (name "unconnected-(IC2L-PE2-Pad1)") (class "Default")
      (node (ref "IC2") (pin "1") (pinfunction "PE2_1") (pintype "bidirectional"))
    )
    (net (code "130") (name "unconnected-(IC2L-PE3-Pad2)") (class "Default")
      (node (ref "IC2") (pin "2") (pinfunction "PE3_2") (pintype "bidirectional"))
    )
    (net (code "131") (name "unconnected-(IC2L-PE4-Pad3)") (class "Default")
      (node (ref "IC2") (pin "3") (pinfunction "PE4_3") (pintype "bidirectional"))
    )
    (net (code "132") (name "unconnected-(IC2L-PE5-Pad4)") (class "Default")
      (node (ref "IC2") (pin "4") (pinfunction "PE5_4") (pintype "bidirectional"))
    )
    (net (code "133") (name "unconnected-(IC2L-PE6-Pad5)") (class "Default")
      (node (ref "IC2") (pin "5") (pinfunction "PE6_5") (pintype "bidirectional"))
    )
    (net (code "134") (name "unconnected-(IC2L-PE7-Pad38)") (class "Default")
      (node (ref "IC2") (pin "38") (pinfunction "PE7_38") (pintype "bidirectional"))
    )
    (net (code "135") (name "unconnected-(U$1-CAP-Pad15)") (class "Default")
      (node (ref "U$1") (pin "15") (pinfunction "CAP_15") (pintype "passive"))
    )
    (net (code "136") (name "unconnected-(U$1-CS_A-Pad23)") (class "Default")
      (node (ref "U$1") (pin "23") (pinfunction "CS_A_23") (pintype "input"))
    )
    (net (code "137") (name "unconnected-(U$1-CS_G-Pad22)") (class "Default")
      (node (ref "U$1") (pin "22") (pinfunction "CS_G_22") (pintype "input"))
    )
    (net (code "138") (name "unconnected-(U$1-DEN_G-Pad16)") (class "Default")
      (node (ref "U$1") (pin "16") (pinfunction "DEN_G_16") (pintype "input"))
    )
    (net (code "139") (name "unconnected-(U$1-DRDY_G{slash}INT2_G-Pad17)") (class "Default")
      (node (ref "U$1") (pin "17") (pinfunction "DRDY_G/INT2_G_17") (pintype "output"))
    )
    (net (code "140") (name "unconnected-(U$1-INT1_A-Pad20)") (class "Default")
      (node (ref "U$1") (pin "20") (pinfunction "INT1_A_20") (pintype "output"))
    )
    (net (code "141") (name "unconnected-(U$1-INT1_G-Pad18)") (class "Default")
      (node (ref "U$1") (pin "18") (pinfunction "INT1_G_18") (pintype "output"))
    )
    (net (code "142") (name "unconnected-(U$1-INT2_A-Pad19)") (class "Default")
      (node (ref "U$1") (pin "19") (pinfunction "INT2_A_19") (pintype "output"))
    )
    (net (code "143") (name "unconnected-(U$1-SCL_A{slash}G-Pad24)") (class "Default")
      (node (ref "U$1") (pin "24") (pinfunction "SCL_A/G_24") (pintype "input"))
    )
    (net (code "144") (name "unconnected-(U$1-SDA_A{slash}G-Pad28)") (class "Default")
      (node (ref "U$1") (pin "28") (pinfunction "SDA_A/G_28") (pintype "input"))
    )
    (net (code "145") (name "unconnected-(U$1-SDO_A-Pad27)") (class "Default")
      (node (ref "U$1") (pin "27") (pinfunction "SDO_A_27") (pintype "output"))
    )
    (net (code "146") (name "unconnected-(U$1-SDO_G-Pad26)") (class "Default")
      (node (ref "U$1") (pin "26") (pinfunction "SDO_G_26") (pintype "output"))
    )
    (net (code "147") (name "unconnected-(X1C-1-Pad11)") (class "Default")
      (node (ref "X1") (pin "11") (pinfunction "1_11") (pintype "passive"))
    )
    (net (code "148") (name "unconnected-(X1T-1-Pad9)") (class "Default")
      (node (ref "X1") (pin "9") (pinfunction "1_9") (pintype "passive"))
    )
  )
)
